# PROG.net
KiCad netlist of a schematic drawn in EAGLE
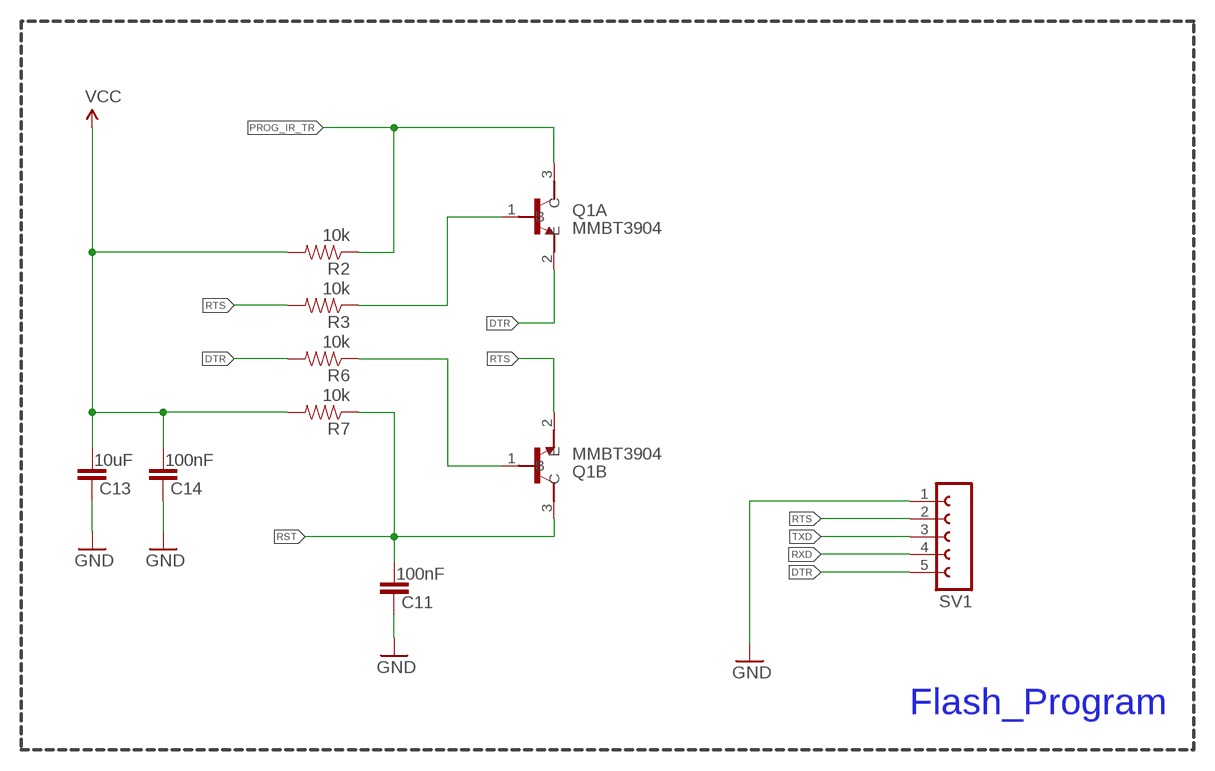
[diagram p0: schematic, sheet 1]

(export (version "E")
  (design (tool "Eeschema 10.0.6"))
  (components
    (comp (ref "C11")
      (value "100nF")
      (footprint "eagle-import:C0805")
      (libsource (lib "eagle-import") (part "C-EUC0805"))
    )
    (comp (ref "C13")
      (value "10uF")
      (footprint "eagle-import:C0805")
      (libsource (lib "eagle-import") (part "C-EUC0805"))
    )
    (comp (ref "C14")
      (value "100nF")
      (footprint "eagle-import:C0805")
      (libsource (lib "eagle-import") (part "C-EUC0805"))
    )
    (comp (ref "Q1A")
      (value "MMBT3904")
      (footprint "eagle-import:SOT95P240X120-3N")
      (fields (field (name "MF") "STMicroelectronics"))
      (libsource (lib "eagle-import") (part "MMBT3904"))
    )
    (comp (ref "Q1B")
      (value "MMBT3904")
      (footprint "eagle-import:SOT95P240X120-3N")
      (fields (field (name "MF") "STMicroelectronics"))
      (libsource (lib "eagle-import") (part "MMBT3904"))
    )
    (comp (ref "R2")
      (value "10k")
      (footprint "eagle-import:SPARKFUN_0805")
      (libsource (lib "eagle-import") (part "SPARKFUN_RESISTOR0805-RES"))
    )
    (comp (ref "R3")
      (value "10k")
      (footprint "eagle-import:SPARKFUN_0805")
      (libsource (lib "eagle-import") (part "SPARKFUN_RESISTOR0805-RES"))
    )
    (comp (ref "R6")
      (value "10k")
      (footprint "eagle-import:SPARKFUN_0805")
      (libsource (lib "eagle-import") (part "SPARKFUN_RESISTOR0805-RES"))
    )
    (comp (ref "R7")
      (value "10k")
      (footprint "eagle-import:SPARKFUN_0805")
      (libsource (lib "eagle-import") (part "SPARKFUN_RESISTOR0805-RES"))
    )
    (comp (ref "SV1")
      (value "FE05-1")
      (footprint "eagle-import:FE05-1")
      (libsource (lib "eagle-import") (part "FE05-1"))
    )
  )
  (nets
    (net (code "1") (name "DTR") (class "Default")
      (node (ref "Q1A") (pin "2") (pinfunction "E_2") (pintype "passive"))
      (node (ref "R6") (pin "2") (pinfunction "2_2") (pintype "passive"))
      (node (ref "SV1") (pin "5") (pinfunction "5_5") (pintype "passive"))
    )
    (net (code "2") (name "GND") (class "Default")
      (node (ref "C11") (pin "1") (pinfunction "1_1") (pintype "passive"))
      (node (ref "C13") (pin "1") (pinfunction "1_1") (pintype "passive"))
      (node (ref "C14") (pin "1") (pinfunction "1_1") (pintype "passive"))
      (node (ref "SV1") (pin "1") (pinfunction "1_1") (pintype "passive"))
    )
    (net (code "3") (name "Net-(Q1A-B)") (class "Default")
      (node (ref "Q1A") (pin "1") (pinfunction "B_1") (pintype "passive"))
      (node (ref "R3") (pin "1") (pinfunction "1_1") (pintype "passive"))
    )
    (net (code "4") (name "Net-(Q1B-B)") (class "Default")
      (node (ref "Q1B") (pin "1") (pinfunction "B_1") (pintype "passive"))
      (node (ref "R6") (pin "1") (pinfunction "1_1") (pintype "passive"))
    )
    (net (code "5") (name "PROG_IR_TR") (class "Default")
      (node (ref "Q1A") (pin "3") (pinfunction "C_3") (pintype "passive"))
      (node (ref "R2") (pin "1") (pinfunction "1_1") (pintype "passive"))
    )
    (net (code "6") (name "RST") (class "Default")
      (node (ref "C11") (pin "2") (pinfunction "2_2") (pintype "passive"))
      (node (ref "Q1B") (pin "3") (pinfunction "C_3") (pintype "passive"))
      (node (ref "R7") (pin "1") (pinfunction "1_1") (pintype "passive"))
    )
    (net (code "7") (name "RTS") (class "Default")
      (node (ref "Q1B") (pin "2") (pinfunction "E_2") (pintype "passive"))
      (node (ref "R3") (pin "2") (pinfunction "2_2") (pintype "passive"))
      (node (ref "SV1") (pin "2") (pinfunction "2_2") (pintype "passive"))
    )
    (net (code "8") (name "RXD") (class "Default")
      (node (ref "SV1") (pin "4") (pinfunction "4_4") (pintype "passive"))
    )
    (net (code "9") (name "TXD") (class "Default")
      (node (ref "SV1") (pin "3") (pinfunction "3_3") (pintype "passive"))
    )
    (net (code "10") (name "VCC") (class "Default")
      (node (ref "C13") (pin "2") (pinfunction "2_2") (pintype "passive"))
      (node (ref "C14") (pin "2") (pinfunction "2_2") (pintype "passive"))
      (node (ref "R2") (pin "2") (pinfunction "2_2") (pintype "passive"))
      (node (ref "R7") (pin "2") (pinfunction "2_2") (pintype "passive"))
    )
  )
)
